# flex_conn_v5.net
KiCad netlist of a schematic drawn in EAGLE
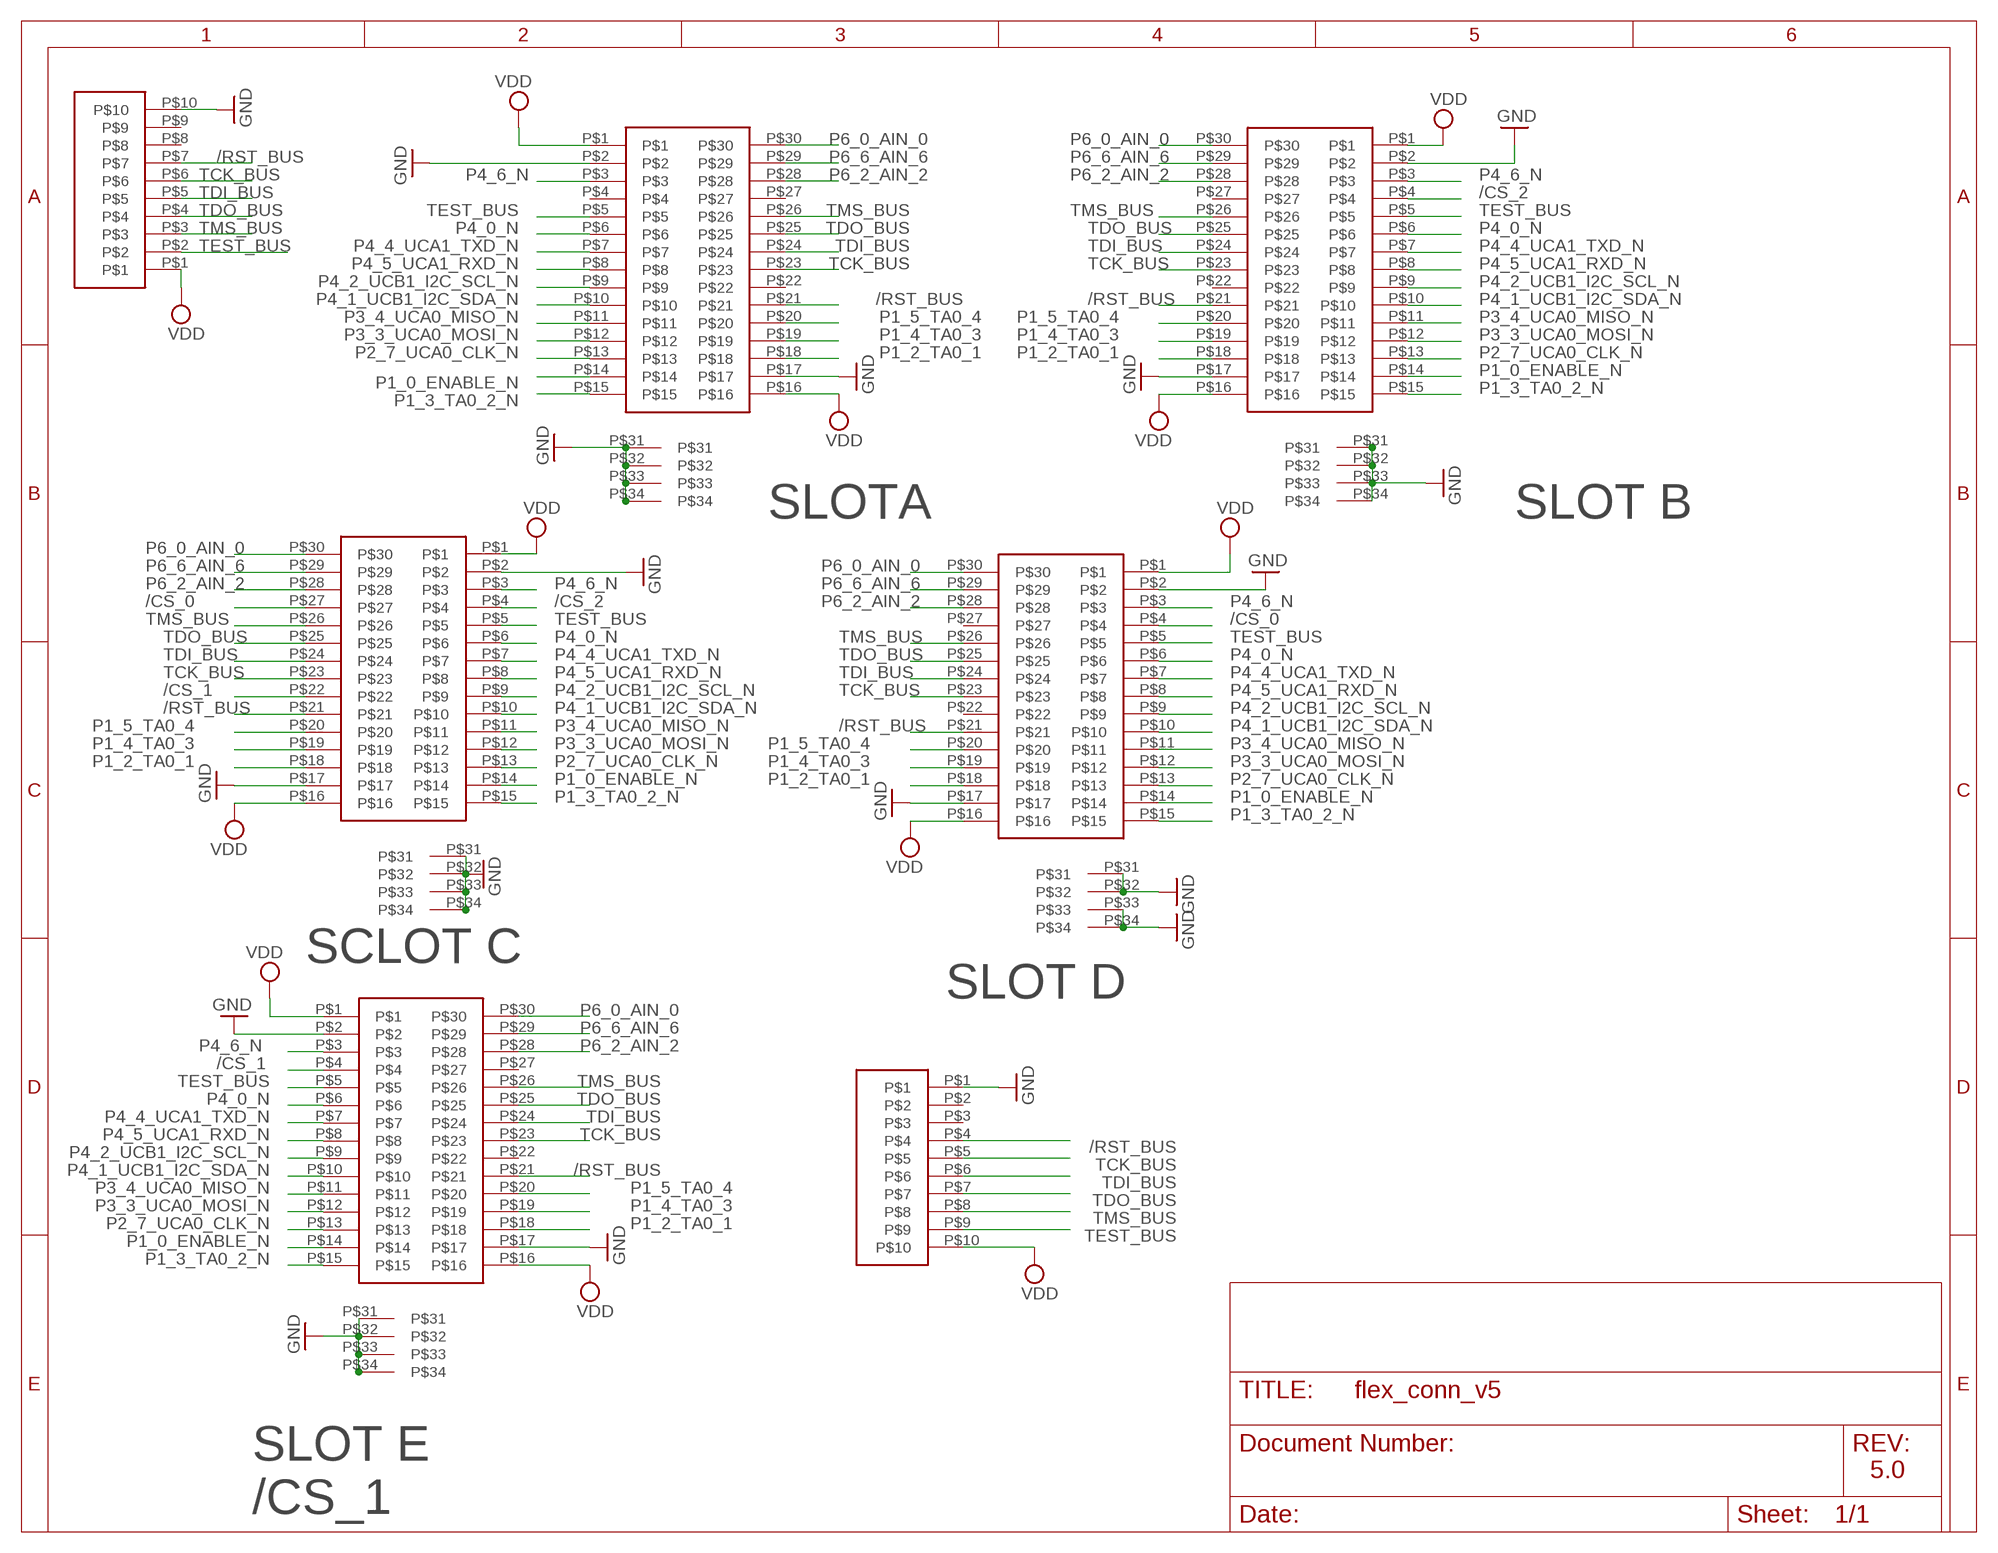
[diagram p0: schematic, sheet 1]

(export (version "E")
  (design (tool "Eeschema 10.0.6"))
  (components
    (comp (ref "U$1")
      (value "500913-0302_REC_30CONN_2")
      (footprint "eagle-import:500913-0302_REC_30CONN_2")
      (libsource (lib "eagle-import") (part "500913-0302_REC_30CONN_2"))
    )
    (comp (ref "U$2")
      (value "500913-0302_REC_30CONN_2")
      (footprint "eagle-import:500913-0302_REC_30CONN_2")
      (libsource (lib "eagle-import") (part "500913-0302_REC_30CONN_2"))
    )
    (comp (ref "U$3")
      (value "500913-0302_REC_30CONN_2")
      (footprint "eagle-import:500913-0302_REC_30CONN_2")
      (libsource (lib "eagle-import") (part "500913-0302_REC_30CONN_2"))
    )
    (comp (ref "U$4")
      (value "500913-0302_REC_30CONN_2")
      (footprint "eagle-import:500913-0302_REC_30CONN_2")
      (libsource (lib "eagle-import") (part "500913-0302_REC_30CONN_2"))
    )
    (comp (ref "U$5")
      (value "CABLE_ADAPTATOR")
      (footprint "eagle-import:FPC_FFC")
      (libsource (lib "eagle-import") (part "CABLE_ADAPTATOR"))
    )
    (comp (ref "U$6")
      (value "500913-0302_REC_30CONN_2")
      (footprint "eagle-import:500913-0302_REC_30CONN_2")
      (libsource (lib "eagle-import") (part "500913-0302_REC_30CONN_2"))
    )
    (comp (ref "U$7")
      (value "CABLE_ADAPTATOR")
      (footprint "eagle-import:FPC_FFC")
      (libsource (lib "eagle-import") (part "CABLE_ADAPTATOR"))
    )
  )
  (nets
    (net (code "1") (name "/P1_0_ENABLE_N") (class "Default")
      (node (ref "U$1") (pin "P$14") (pinfunction "P$14_P$14") (pintype "bidirectional"))
      (node (ref "U$2") (pin "P$14") (pinfunction "P$14_P$14") (pintype "bidirectional"))
      (node (ref "U$3") (pin "P$14") (pinfunction "P$14_P$14") (pintype "bidirectional"))
      (node (ref "U$4") (pin "P$14") (pinfunction "P$14_P$14") (pintype "bidirectional"))
      (node (ref "U$6") (pin "P$14") (pinfunction "P$14_P$14") (pintype "bidirectional"))
    )
    (net (code "2") (name "/P1_2_TA0_1") (class "Default")
      (node (ref "U$1") (pin "P$18") (pinfunction "P$18_P$18") (pintype "bidirectional"))
      (node (ref "U$2") (pin "P$18") (pinfunction "P$18_P$18") (pintype "bidirectional"))
      (node (ref "U$3") (pin "P$18") (pinfunction "P$18_P$18") (pintype "bidirectional"))
      (node (ref "U$4") (pin "P$18") (pinfunction "P$18_P$18") (pintype "bidirectional"))
      (node (ref "U$6") (pin "P$18") (pinfunction "P$18_P$18") (pintype "bidirectional"))
    )
    (net (code "3") (name "/P1_3_TA0_2_N") (class "Default")
      (node (ref "U$1") (pin "P$15") (pinfunction "P$15_P$15") (pintype "bidirectional"))
      (node (ref "U$2") (pin "P$15") (pinfunction "P$15_P$15") (pintype "bidirectional"))
      (node (ref "U$3") (pin "P$15") (pinfunction "P$15_P$15") (pintype "bidirectional"))
      (node (ref "U$4") (pin "P$15") (pinfunction "P$15_P$15") (pintype "bidirectional"))
      (node (ref "U$6") (pin "P$15") (pinfunction "P$15_P$15") (pintype "bidirectional"))
    )
    (net (code "4") (name "/P1_4_TA0_3") (class "Default")
      (node (ref "U$1") (pin "P$19") (pinfunction "P$19_P$19") (pintype "bidirectional"))
      (node (ref "U$2") (pin "P$19") (pinfunction "P$19_P$19") (pintype "bidirectional"))
      (node (ref "U$3") (pin "P$19") (pinfunction "P$19_P$19") (pintype "bidirectional"))
      (node (ref "U$4") (pin "P$19") (pinfunction "P$19_P$19") (pintype "bidirectional"))
      (node (ref "U$6") (pin "P$19") (pinfunction "P$19_P$19") (pintype "bidirectional"))
    )
    (net (code "5") (name "/P1_5_TA0_4") (class "Default")
      (node (ref "U$1") (pin "P$20") (pinfunction "P$20_P$20") (pintype "bidirectional"))
      (node (ref "U$2") (pin "P$20") (pinfunction "P$20_P$20") (pintype "bidirectional"))
      (node (ref "U$3") (pin "P$20") (pinfunction "P$20_P$20") (pintype "bidirectional"))
      (node (ref "U$4") (pin "P$20") (pinfunction "P$20_P$20") (pintype "bidirectional"))
      (node (ref "U$6") (pin "P$20") (pinfunction "P$20_P$20") (pintype "bidirectional"))
    )
    (net (code "6") (name "/P2_7_UCA0_CLK_N") (class "Default")
      (node (ref "U$1") (pin "P$13") (pinfunction "P$13_P$13") (pintype "bidirectional"))
      (node (ref "U$2") (pin "P$13") (pinfunction "P$13_P$13") (pintype "bidirectional"))
      (node (ref "U$3") (pin "P$13") (pinfunction "P$13_P$13") (pintype "bidirectional"))
      (node (ref "U$4") (pin "P$13") (pinfunction "P$13_P$13") (pintype "bidirectional"))
      (node (ref "U$6") (pin "P$13") (pinfunction "P$13_P$13") (pintype "bidirectional"))
    )
    (net (code "7") (name "/P3_3_UCA0_MOSI_N") (class "Default")
      (node (ref "U$1") (pin "P$12") (pinfunction "P$12_P$12") (pintype "bidirectional"))
      (node (ref "U$2") (pin "P$12") (pinfunction "P$12_P$12") (pintype "bidirectional"))
      (node (ref "U$3") (pin "P$12") (pinfunction "P$12_P$12") (pintype "bidirectional"))
      (node (ref "U$4") (pin "P$12") (pinfunction "P$12_P$12") (pintype "bidirectional"))
      (node (ref "U$6") (pin "P$12") (pinfunction "P$12_P$12") (pintype "bidirectional"))
    )
    (net (code "8") (name "/P3_4_UCA0_MISO_N") (class "Default")
      (node (ref "U$1") (pin "P$11") (pinfunction "P$11_P$11") (pintype "bidirectional"))
      (node (ref "U$2") (pin "P$11") (pinfunction "P$11_P$11") (pintype "bidirectional"))
      (node (ref "U$3") (pin "P$11") (pinfunction "P$11_P$11") (pintype "bidirectional"))
      (node (ref "U$4") (pin "P$11") (pinfunction "P$11_P$11") (pintype "bidirectional"))
      (node (ref "U$6") (pin "P$11") (pinfunction "P$11_P$11") (pintype "bidirectional"))
    )
    (net (code "9") (name "/P4_0_N") (class "Default")
      (node (ref "U$1") (pin "P$6") (pinfunction "P$6_P$6") (pintype "bidirectional"))
      (node (ref "U$2") (pin "P$6") (pinfunction "P$6_P$6") (pintype "bidirectional"))
      (node (ref "U$3") (pin "P$6") (pinfunction "P$6_P$6") (pintype "bidirectional"))
      (node (ref "U$4") (pin "P$6") (pinfunction "P$6_P$6") (pintype "bidirectional"))
      (node (ref "U$6") (pin "P$6") (pinfunction "P$6_P$6") (pintype "bidirectional"))
    )
    (net (code "10") (name "/P4_1_UCB1_I2C_SDA_N") (class "Default")
      (node (ref "U$1") (pin "P$10") (pinfunction "P$10_P$10") (pintype "bidirectional"))
      (node (ref "U$2") (pin "P$10") (pinfunction "P$10_P$10") (pintype "bidirectional"))
      (node (ref "U$3") (pin "P$10") (pinfunction "P$10_P$10") (pintype "bidirectional"))
      (node (ref "U$4") (pin "P$10") (pinfunction "P$10_P$10") (pintype "bidirectional"))
      (node (ref "U$6") (pin "P$10") (pinfunction "P$10_P$10") (pintype "bidirectional"))
    )
    (net (code "11") (name "/P4_2_UCB1_I2C_SCL_N") (class "Default")
      (node (ref "U$1") (pin "P$9") (pinfunction "P$9_P$9") (pintype "bidirectional"))
      (node (ref "U$2") (pin "P$9") (pinfunction "P$9_P$9") (pintype "bidirectional"))
      (node (ref "U$3") (pin "P$9") (pinfunction "P$9_P$9") (pintype "bidirectional"))
      (node (ref "U$4") (pin "P$9") (pinfunction "P$9_P$9") (pintype "bidirectional"))
      (node (ref "U$6") (pin "P$9") (pinfunction "P$9_P$9") (pintype "bidirectional"))
    )
    (net (code "12") (name "/P4_4_UCA1_TXD_N") (class "Default")
      (node (ref "U$1") (pin "P$7") (pinfunction "P$7_P$7") (pintype "bidirectional"))
      (node (ref "U$2") (pin "P$7") (pinfunction "P$7_P$7") (pintype "bidirectional"))
      (node (ref "U$3") (pin "P$7") (pinfunction "P$7_P$7") (pintype "bidirectional"))
      (node (ref "U$4") (pin "P$7") (pinfunction "P$7_P$7") (pintype "bidirectional"))
      (node (ref "U$6") (pin "P$7") (pinfunction "P$7_P$7") (pintype "bidirectional"))
    )
    (net (code "13") (name "/P4_5_UCA1_RXD_N") (class "Default")
      (node (ref "U$1") (pin "P$8") (pinfunction "P$8_P$8") (pintype "bidirectional"))
      (node (ref "U$2") (pin "P$8") (pinfunction "P$8_P$8") (pintype "bidirectional"))
      (node (ref "U$3") (pin "P$8") (pinfunction "P$8_P$8") (pintype "bidirectional"))
      (node (ref "U$4") (pin "P$8") (pinfunction "P$8_P$8") (pintype "bidirectional"))
      (node (ref "U$6") (pin "P$8") (pinfunction "P$8_P$8") (pintype "bidirectional"))
    )
    (net (code "14") (name "/P4_6_N") (class "Default")
      (node (ref "U$1") (pin "P$3") (pinfunction "P$3_P$3") (pintype "bidirectional"))
      (node (ref "U$2") (pin "P$3") (pinfunction "P$3_P$3") (pintype "bidirectional"))
      (node (ref "U$3") (pin "P$3") (pinfunction "P$3_P$3") (pintype "bidirectional"))
      (node (ref "U$4") (pin "P$3") (pinfunction "P$3_P$3") (pintype "bidirectional"))
      (node (ref "U$6") (pin "P$3") (pinfunction "P$3_P$3") (pintype "bidirectional"))
    )
    (net (code "15") (name "/P6_0_AIN_0") (class "Default")
      (node (ref "U$1") (pin "P$30") (pinfunction "P$30_P$30") (pintype "bidirectional"))
      (node (ref "U$2") (pin "P$30") (pinfunction "P$30_P$30") (pintype "bidirectional"))
      (node (ref "U$3") (pin "P$30") (pinfunction "P$30_P$30") (pintype "bidirectional"))
      (node (ref "U$4") (pin "P$30") (pinfunction "P$30_P$30") (pintype "bidirectional"))
      (node (ref "U$6") (pin "P$30") (pinfunction "P$30_P$30") (pintype "bidirectional"))
    )
    (net (code "16") (name "/P6_2_AIN_2") (class "Default")
      (node (ref "U$1") (pin "P$28") (pinfunction "P$28_P$28") (pintype "bidirectional"))
      (node (ref "U$2") (pin "P$28") (pinfunction "P$28_P$28") (pintype "bidirectional"))
      (node (ref "U$3") (pin "P$28") (pinfunction "P$28_P$28") (pintype "bidirectional"))
      (node (ref "U$4") (pin "P$28") (pinfunction "P$28_P$28") (pintype "bidirectional"))
      (node (ref "U$6") (pin "P$28") (pinfunction "P$28_P$28") (pintype "bidirectional"))
    )
    (net (code "17") (name "/P6_6_AIN_6") (class "Default")
      (node (ref "U$1") (pin "P$29") (pinfunction "P$29_P$29") (pintype "bidirectional"))
      (node (ref "U$2") (pin "P$29") (pinfunction "P$29_P$29") (pintype "bidirectional"))
      (node (ref "U$3") (pin "P$29") (pinfunction "P$29_P$29") (pintype "bidirectional"))
      (node (ref "U$4") (pin "P$29") (pinfunction "P$29_P$29") (pintype "bidirectional"))
      (node (ref "U$6") (pin "P$29") (pinfunction "P$29_P$29") (pintype "bidirectional"))
    )
    (net (code "18") (name "/TCK_BUS") (class "Default")
      (node (ref "U$1") (pin "P$23") (pinfunction "P$23_P$23") (pintype "bidirectional"))
      (node (ref "U$2") (pin "P$23") (pinfunction "P$23_P$23") (pintype "bidirectional"))
      (node (ref "U$3") (pin "P$23") (pinfunction "P$23_P$23") (pintype "bidirectional"))
      (node (ref "U$4") (pin "P$23") (pinfunction "P$23_P$23") (pintype "bidirectional"))
      (node (ref "U$5") (pin "P$6") (pinfunction "P$6_P$6") (pintype "bidirectional"))
      (node (ref "U$6") (pin "P$23") (pinfunction "P$23_P$23") (pintype "bidirectional"))
      (node (ref "U$7") (pin "P$5") (pinfunction "P$5_P$5") (pintype "bidirectional"))
    )
    (net (code "19") (name "/TDI_BUS") (class "Default")
      (node (ref "U$1") (pin "P$24") (pinfunction "P$24_P$24") (pintype "bidirectional"))
      (node (ref "U$2") (pin "P$24") (pinfunction "P$24_P$24") (pintype "bidirectional"))
      (node (ref "U$3") (pin "P$24") (pinfunction "P$24_P$24") (pintype "bidirectional"))
      (node (ref "U$4") (pin "P$24") (pinfunction "P$24_P$24") (pintype "bidirectional"))
      (node (ref "U$5") (pin "P$5") (pinfunction "P$5_P$5") (pintype "bidirectional"))
      (node (ref "U$6") (pin "P$24") (pinfunction "P$24_P$24") (pintype "bidirectional"))
      (node (ref "U$7") (pin "P$6") (pinfunction "P$6_P$6") (pintype "bidirectional"))
    )
    (net (code "20") (name "/TDO_BUS") (class "Default")
      (node (ref "U$1") (pin "P$25") (pinfunction "P$25_P$25") (pintype "bidirectional"))
      (node (ref "U$2") (pin "P$25") (pinfunction "P$25_P$25") (pintype "bidirectional"))
      (node (ref "U$3") (pin "P$25") (pinfunction "P$25_P$25") (pintype "bidirectional"))
      (node (ref "U$4") (pin "P$25") (pinfunction "P$25_P$25") (pintype "bidirectional"))
      (node (ref "U$5") (pin "P$4") (pinfunction "P$4_P$4") (pintype "bidirectional"))
      (node (ref "U$6") (pin "P$25") (pinfunction "P$25_P$25") (pintype "bidirectional"))
      (node (ref "U$7") (pin "P$7") (pinfunction "P$7_P$7") (pintype "bidirectional"))
    )
    (net (code "21") (name "/TEST_BUS") (class "Default")
      (node (ref "U$1") (pin "P$5") (pinfunction "P$5_P$5") (pintype "bidirectional"))
      (node (ref "U$2") (pin "P$5") (pinfunction "P$5_P$5") (pintype "bidirectional"))
      (node (ref "U$3") (pin "P$5") (pinfunction "P$5_P$5") (pintype "bidirectional"))
      (node (ref "U$4") (pin "P$5") (pinfunction "P$5_P$5") (pintype "bidirectional"))
      (node (ref "U$5") (pin "P$2") (pinfunction "P$2_P$2") (pintype "bidirectional"))
      (node (ref "U$6") (pin "P$5") (pinfunction "P$5_P$5") (pintype "bidirectional"))
      (node (ref "U$7") (pin "P$9") (pinfunction "P$9_P$9") (pintype "bidirectional"))
    )
    (net (code "22") (name "/TMS_BUS") (class "Default")
      (node (ref "U$1") (pin "P$26") (pinfunction "P$26_P$26") (pintype "bidirectional"))
      (node (ref "U$2") (pin "P$26") (pinfunction "P$26_P$26") (pintype "bidirectional"))
      (node (ref "U$3") (pin "P$26") (pinfunction "P$26_P$26") (pintype "bidirectional"))
      (node (ref "U$4") (pin "P$26") (pinfunction "P$26_P$26") (pintype "bidirectional"))
      (node (ref "U$5") (pin "P$3") (pinfunction "P$3_P$3") (pintype "bidirectional"))
      (node (ref "U$6") (pin "P$26") (pinfunction "P$26_P$26") (pintype "bidirectional"))
      (node (ref "U$7") (pin "P$8") (pinfunction "P$8_P$8") (pintype "bidirectional"))
    )
    (net (code "23") (name "/{slash}CS_0") (class "Default")
      (node (ref "U$1") (pin "P$4") (pinfunction "P$4_P$4") (pintype "bidirectional"))
      (node (ref "U$6") (pin "P$27") (pinfunction "P$27_P$27") (pintype "bidirectional"))
    )
    (net (code "24") (name "/{slash}CS_1") (class "Default")
      (node (ref "U$4") (pin "P$4") (pinfunction "P$4_P$4") (pintype "bidirectional"))
      (node (ref "U$6") (pin "P$22") (pinfunction "P$22_P$22") (pintype "bidirectional"))
    )
    (net (code "25") (name "/{slash}CS_2") (class "Default")
      (node (ref "U$2") (pin "P$4") (pinfunction "P$4_P$4") (pintype "bidirectional"))
      (node (ref "U$6") (pin "P$4") (pinfunction "P$4_P$4") (pintype "bidirectional"))
    )
    (net (code "26") (name "/{slash}RST_BUS") (class "Default")
      (node (ref "U$1") (pin "P$21") (pinfunction "P$21_P$21") (pintype "bidirectional"))
      (node (ref "U$2") (pin "P$21") (pinfunction "P$21_P$21") (pintype "bidirectional"))
      (node (ref "U$3") (pin "P$21") (pinfunction "P$21_P$21") (pintype "bidirectional"))
      (node (ref "U$4") (pin "P$21") (pinfunction "P$21_P$21") (pintype "bidirectional"))
      (node (ref "U$5") (pin "P$7") (pinfunction "P$7_P$7") (pintype "bidirectional"))
      (node (ref "U$6") (pin "P$21") (pinfunction "P$21_P$21") (pintype "bidirectional"))
      (node (ref "U$7") (pin "P$4") (pinfunction "P$4_P$4") (pintype "bidirectional"))
    )
    (net (code "27") (name "GND") (class "Default")
      (node (ref "U$1") (pin "P$17") (pinfunction "P$17_P$17") (pintype "bidirectional"))
      (node (ref "U$1") (pin "P$2") (pinfunction "P$2_P$2") (pintype "bidirectional"))
      (node (ref "U$1") (pin "P$31") (pinfunction "P$31_P$31") (pintype "bidirectional"))
      (node (ref "U$1") (pin "P$32") (pinfunction "P$32_P$32") (pintype "bidirectional"))
      (node (ref "U$1") (pin "P$33") (pinfunction "P$33_P$33") (pintype "bidirectional"))
      (node (ref "U$1") (pin "P$34") (pinfunction "P$34_P$34") (pintype "bidirectional"))
      (node (ref "U$2") (pin "P$17") (pinfunction "P$17_P$17") (pintype "bidirectional"))
      (node (ref "U$2") (pin "P$2") (pinfunction "P$2_P$2") (pintype "bidirectional"))
      (node (ref "U$2") (pin "P$31") (pinfunction "P$31_P$31") (pintype "bidirectional"))
      (node (ref "U$2") (pin "P$32") (pinfunction "P$32_P$32") (pintype "bidirectional"))
      (node (ref "U$2") (pin "P$33") (pinfunction "P$33_P$33") (pintype "bidirectional"))
      (node (ref "U$2") (pin "P$34") (pinfunction "P$34_P$34") (pintype "bidirectional"))
      (node (ref "U$3") (pin "P$17") (pinfunction "P$17_P$17") (pintype "bidirectional"))
      (node (ref "U$3") (pin "P$2") (pinfunction "P$2_P$2") (pintype "bidirectional"))
      (node (ref "U$3") (pin "P$31") (pinfunction "P$31_P$31") (pintype "bidirectional"))
      (node (ref "U$3") (pin "P$32") (pinfunction "P$32_P$32") (pintype "bidirectional"))
      (node (ref "U$3") (pin "P$33") (pinfunction "P$33_P$33") (pintype "bidirectional"))
      (node (ref "U$3") (pin "P$34") (pinfunction "P$34_P$34") (pintype "bidirectional"))
      (node (ref "U$4") (pin "P$17") (pinfunction "P$17_P$17") (pintype "bidirectional"))
      (node (ref "U$4") (pin "P$2") (pinfunction "P$2_P$2") (pintype "bidirectional"))
      (node (ref "U$4") (pin "P$31") (pinfunction "P$31_P$31") (pintype "bidirectional"))
      (node (ref "U$4") (pin "P$32") (pinfunction "P$32_P$32") (pintype "bidirectional"))
      (node (ref "U$4") (pin "P$33") (pinfunction "P$33_P$33") (pintype "bidirectional"))
      (node (ref "U$4") (pin "P$34") (pinfunction "P$34_P$34") (pintype "bidirectional"))
      (node (ref "U$5") (pin "P$10") (pinfunction "P$10_P$10") (pintype "bidirectional"))
      (node (ref "U$6") (pin "P$17") (pinfunction "P$17_P$17") (pintype "bidirectional"))
      (node (ref "U$6") (pin "P$2") (pinfunction "P$2_P$2") (pintype "bidirectional"))
      (node (ref "U$6") (pin "P$31") (pinfunction "P$31_P$31") (pintype "bidirectional"))
      (node (ref "U$6") (pin "P$32") (pinfunction "P$32_P$32") (pintype "bidirectional"))
      (node (ref "U$6") (pin "P$33") (pinfunction "P$33_P$33") (pintype "bidirectional"))
      (node (ref "U$6") (pin "P$34") (pinfunction "P$34_P$34") (pintype "bidirectional"))
      (node (ref "U$7") (pin "P$1") (pinfunction "P$1_P$1") (pintype "bidirectional"))
    )
    (net (code "28") (name "VDD") (class "Default")
      (node (ref "U$1") (pin "P$1") (pinfunction "P$1_P$1") (pintype "bidirectional"))
      (node (ref "U$1") (pin "P$16") (pinfunction "P$16_P$16") (pintype "bidirectional"))
      (node (ref "U$2") (pin "P$1") (pinfunction "P$1_P$1") (pintype "bidirectional"))
      (node (ref "U$2") (pin "P$16") (pinfunction "P$16_P$16") (pintype "bidirectional"))
      (node (ref "U$3") (pin "P$1") (pinfunction "P$1_P$1") (pintype "bidirectional"))
      (node (ref "U$3") (pin "P$16") (pinfunction "P$16_P$16") (pintype "bidirectional"))
      (node (ref "U$4") (pin "P$1") (pinfunction "P$1_P$1") (pintype "bidirectional"))
      (node (ref "U$4") (pin "P$16") (pinfunction "P$16_P$16") (pintype "bidirectional"))
      (node (ref "U$5") (pin "P$1") (pinfunction "P$1_P$1") (pintype "bidirectional"))
      (node (ref "U$6") (pin "P$1") (pinfunction "P$1_P$1") (pintype "bidirectional"))
      (node (ref "U$6") (pin "P$16") (pinfunction "P$16_P$16") (pintype "bidirectional"))
      (node (ref "U$7") (pin "P$10") (pinfunction "P$10_P$10") (pintype "bidirectional"))
    )
    (net (code "29") (name "unconnected-(U$1-PadP$22)") (class "Default")
      (node (ref "U$1") (pin "P$22") (pinfunction "P$22_P$22") (pintype "bidirectional"))
    )
    (net (code "30") (name "unconnected-(U$1-PadP$27)") (class "Default")
      (node (ref "U$1") (pin "P$27") (pinfunction "P$27_P$27") (pintype "bidirectional"))
    )
    (net (code "31") (name "unconnected-(U$2-PadP$22)") (class "Default")
      (node (ref "U$2") (pin "P$22") (pinfunction "P$22_P$22") (pintype "bidirectional"))
    )
    (net (code "32") (name "unconnected-(U$2-PadP$27)") (class "Default")
      (node (ref "U$2") (pin "P$27") (pinfunction "P$27_P$27") (pintype "bidirectional"))
    )
    (net (code "33") (name "unconnected-(U$3-PadP$4)") (class "Default")
      (node (ref "U$3") (pin "P$4") (pinfunction "P$4_P$4") (pintype "bidirectional"))
    )
    (net (code "34") (name "unconnected-(U$3-PadP$22)") (class "Default")
      (node (ref "U$3") (pin "P$22") (pinfunction "P$22_P$22") (pintype "bidirectional"))
    )
    (net (code "35") (name "unconnected-(U$3-PadP$27)") (class "Default")
      (node (ref "U$3") (pin "P$27") (pinfunction "P$27_P$27") (pintype "bidirectional"))
    )
    (net (code "36") (name "unconnected-(U$4-PadP$22)") (class "Default")
      (node (ref "U$4") (pin "P$22") (pinfunction "P$22_P$22") (pintype "bidirectional"))
    )
    (net (code "37") (name "unconnected-(U$4-PadP$27)") (class "Default")
      (node (ref "U$4") (pin "P$27") (pinfunction "P$27_P$27") (pintype "bidirectional"))
    )
    (net (code "38") (name "unconnected-(U$5-PadP$8)") (class "Default")
      (node (ref "U$5") (pin "P$8") (pinfunction "P$8_P$8") (pintype "bidirectional"))
    )
    (net (code "39") (name "unconnected-(U$5-PadP$9)") (class "Default")
      (node (ref "U$5") (pin "P$9") (pinfunction "P$9_P$9") (pintype "bidirectional"))
    )
    (net (code "40") (name "unconnected-(U$7-PadP$2)") (class "Default")
      (node (ref "U$7") (pin "P$2") (pinfunction "P$2_P$2") (pintype "bidirectional"))
    )
    (net (code "41") (name "unconnected-(U$7-PadP$3)") (class "Default")
      (node (ref "U$7") (pin "P$3") (pinfunction "P$3_P$3") (pintype "bidirectional"))
    )
  )
)
